# USB2DAC_PCB.net
KiCad netlist of a schematic drawn in EAGLE
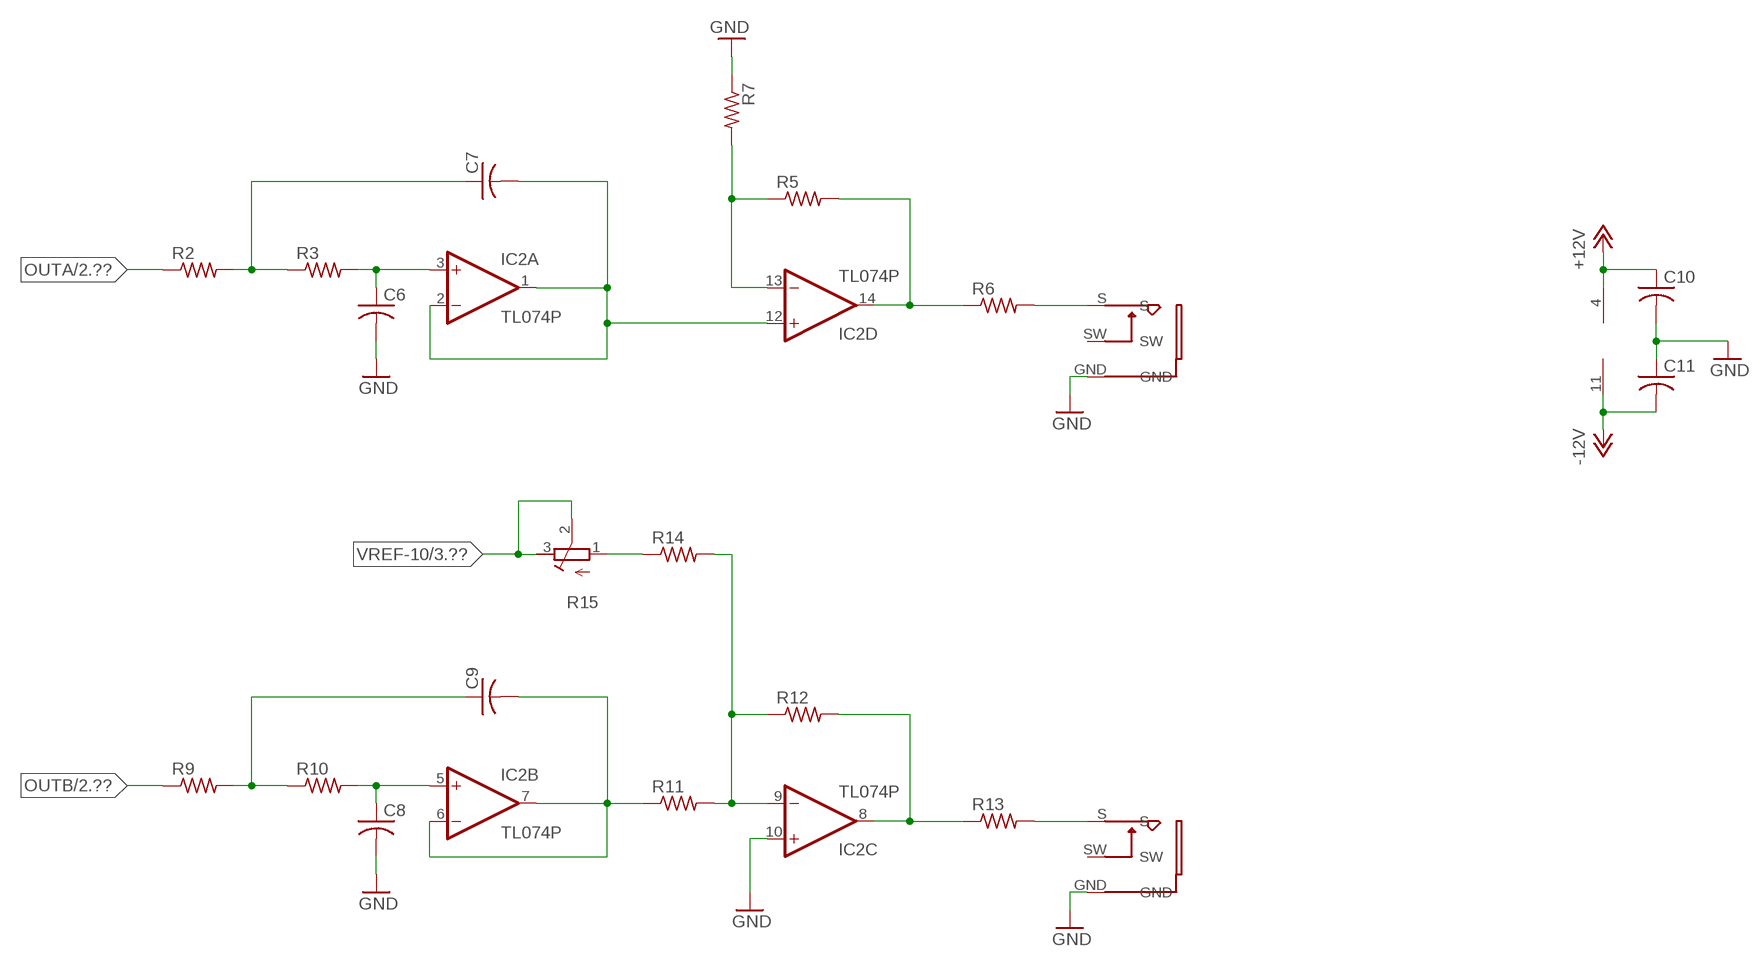
[diagram p0: schematic, sheet 1]
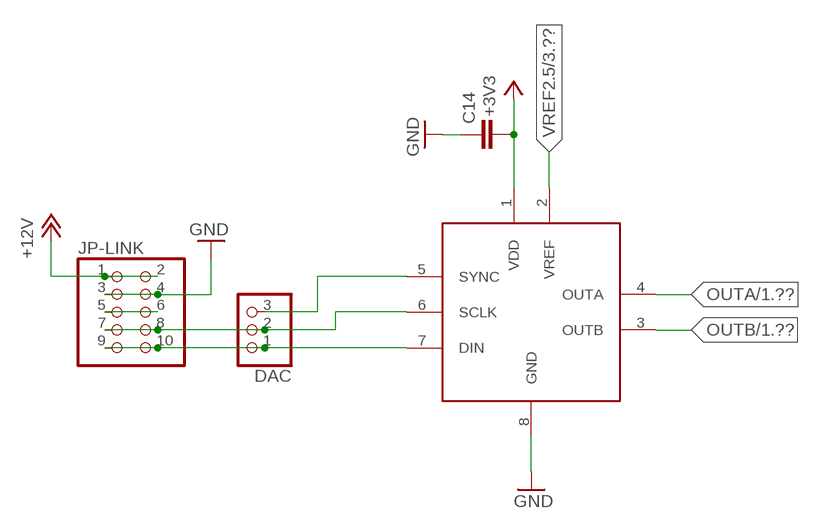
[diagram p1: schematic, sheet 2]
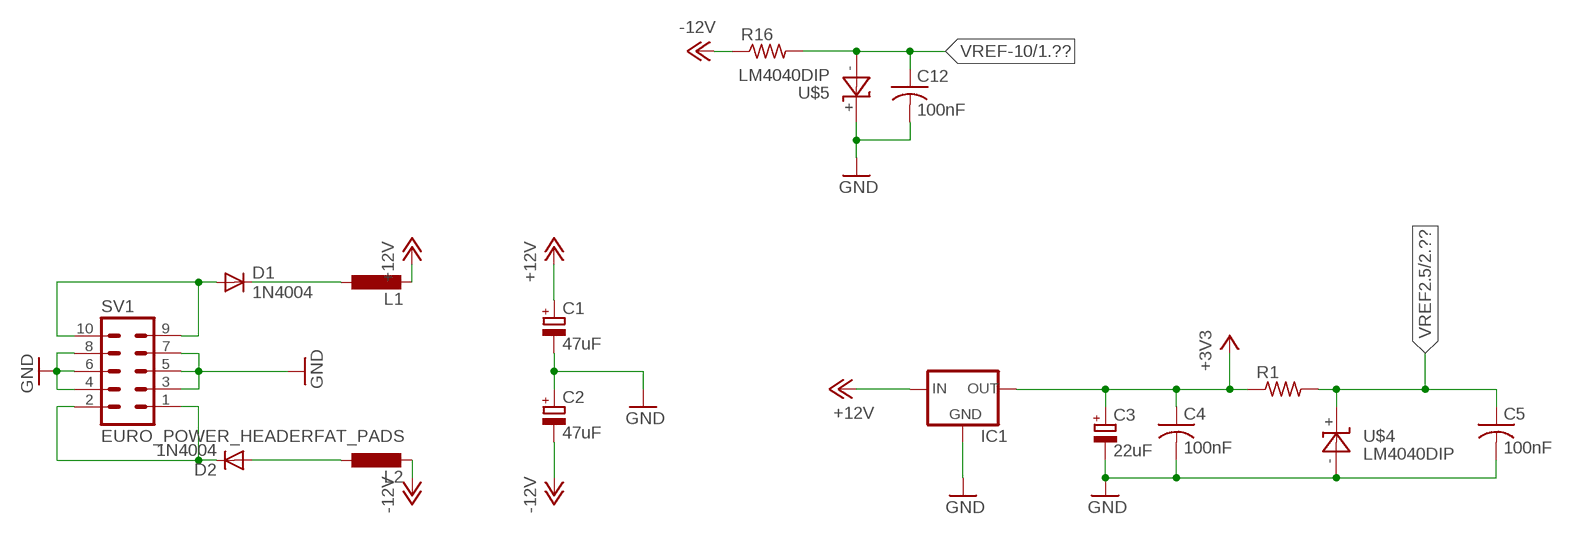
[diagram p2: schematic, sheet 3]
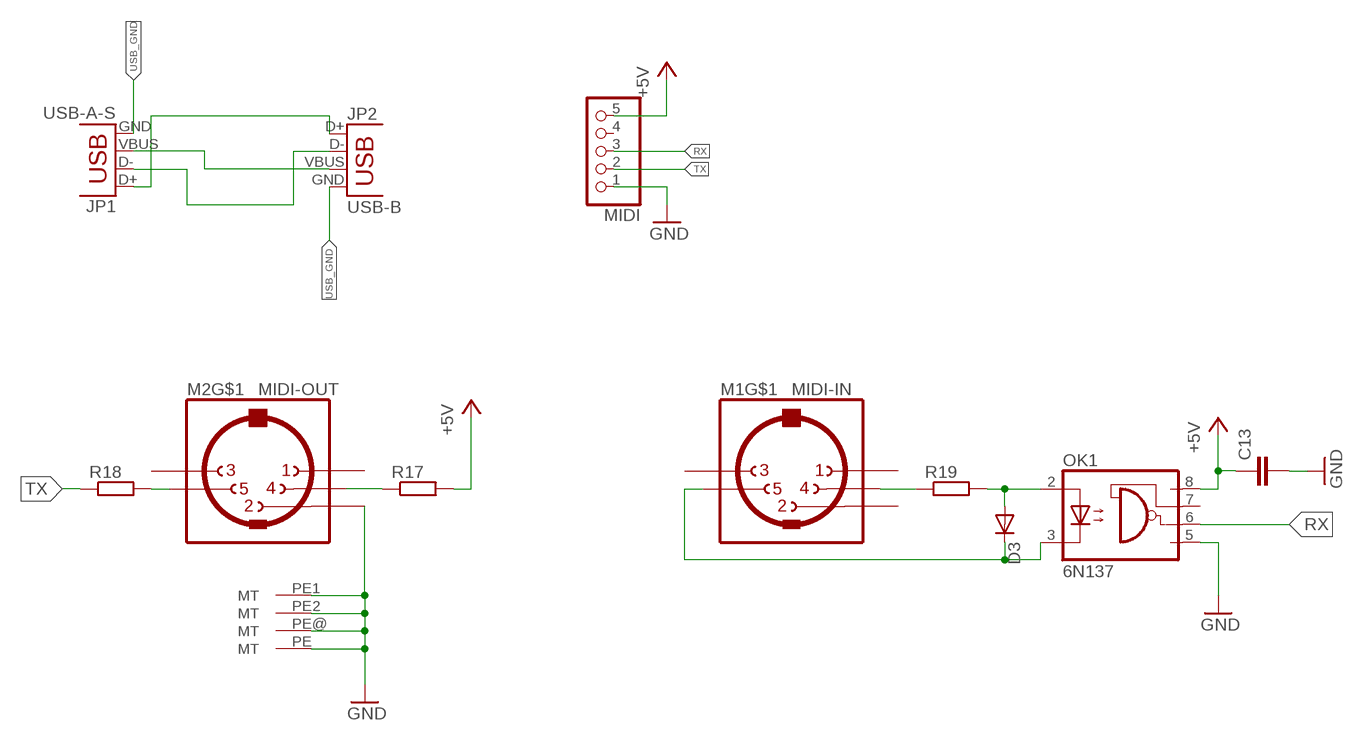
[diagram p3: schematic, sheet 4]

(export (version "E")
  (design (tool "Eeschema 10.0.6"))
  (components
    (comp (ref "C1")
      (value "47uF")
      (footprint "eagle-import:E2-5")
      (libsource (lib "eagle-import") (part "CPOL-EUE2-5"))
    )
    (comp (ref "C2")
      (value "47uF")
      (footprint "eagle-import:E2-5")
      (libsource (lib "eagle-import") (part "CPOL-EUE2-5"))
    )
    (comp (ref "C3")
      (value "22uF")
      (footprint "eagle-import:E2-5")
      (libsource (lib "eagle-import") (part "CPOL-EUE2-5"))
    )
    (comp (ref "C4")
      (value "100nF")
      (footprint "eagle-import:C1206K")
      (libsource (lib "eagle-import") (part "C-USC1206K"))
    )
    (comp (ref "C5")
      (value "100nF")
      (footprint "eagle-import:C1206K")
      (libsource (lib "eagle-import") (part "C-USC1206K"))
    )
    (comp (ref "C12")
      (value "100nF")
      (footprint "eagle-import:C1206K")
      (libsource (lib "eagle-import") (part "C-USC1206K"))
    )
    (comp (ref "D1")
      (value "1N4004")
      (footprint "eagle-import:DO41-10")
      (libsource (lib "eagle-import") (part "1N4004"))
    )
    (comp (ref "D2")
      (value "1N4004")
      (footprint "eagle-import:DO41-10")
      (libsource (lib "eagle-import") (part "1N4004"))
    )
    (comp (ref "IC1")
      (value "78LXX")
      (footprint "eagle-import:78LXX")
      (libsource (lib "eagle-import") (part "78LXX"))
    )
    (comp (ref "L1")
      (value "L-EU0207/10")
      (footprint "eagle-import:0207_10")
      (libsource (lib "eagle-import") (part "L-EU0207/10"))
    )
    (comp (ref "L2")
      (value "L-EU0207/10")
      (footprint "eagle-import:0207_10")
      (libsource (lib "eagle-import") (part "L-EU0207/10"))
    )
    (comp (ref "R1")
      (value "R-US_R1206")
      (footprint "eagle-import:R1206")
      (libsource (lib "eagle-import") (part "R-US_R1206"))
    )
    (comp (ref "R16")
      (value "R-US_R1206")
      (footprint "eagle-import:R1206")
      (libsource (lib "eagle-import") (part "R-US_R1206"))
    )
    (comp (ref "SV1")
      (value "EURO_POWER_HEADERFAT_PADS")
      (footprint "eagle-import:EURO_PWR_HEADER_FAT")
      (libsource (lib "eagle-import") (part "EURO_POWER_HEADERFAT_PADS"))
    )
    (comp (ref "U$4")
      (value "LM4040DIP")
      (footprint "eagle-import:TO-92")
      (libsource (lib "eagle-import") (part "LM4040DIP"))
    )
    (comp (ref "U$5")
      (value "LM4040DIP")
      (footprint "eagle-import:TO-92")
      (libsource (lib "eagle-import") (part "LM4040DIP"))
    )
    (comp (ref "C13")
      (value "C-EUC1206K")
      (footprint "eagle-import:C1206K")
      (libsource (lib "eagle-import") (part "C-EUC1206K"))
    )
    (comp (ref "D3")
      (value "SMALL_DIODEDO35-7")
      (footprint "eagle-import:DO35-7")
      (libsource (lib "eagle-import") (part "SMALL_DIODEDO35-7"))
    )
    (comp (ref "JP1")
      (value "USB-A-S")
      (footprint "eagle-import:USB-A-S")
      (libsource (lib "eagle-import") (part "USB-A-S"))
    )
    (comp (ref "JP2")
      (value "USB-B")
      (footprint "eagle-import:USB-B-PTH")
      (libsource (lib "eagle-import") (part "USBPTH"))
    )
    (comp (ref "M1")
      (value "MIDI-IN")
      (footprint "eagle-import:CP-2350")
      (libsource (lib "eagle-import") (part "MIDIJACK"))
    )
    (comp (ref "M2")
      (value "MIDI-OUT")
      (footprint "eagle-import:CP-2350")
      (libsource (lib "eagle-import") (part "MIDIJACK"))
    )
    (comp (ref "MIDI")
      (value "PINHD-1X5_2.54")
      (footprint "eagle-import:1X05")
      (libsource (lib "eagle-import") (part "PINHD-1X5_2.54"))
    )
    (comp (ref "OK1")
      (value "6N137")
      (footprint "eagle-import:DIL08")
      (libsource (lib "eagle-import") (part "6N137"))
    )
    (comp (ref "R17")
      (value "R-EU_R1206")
      (footprint "eagle-import:R1206")
      (libsource (lib "eagle-import") (part "R-EU_R1206"))
    )
    (comp (ref "R18")
      (value "R-EU_R1206")
      (footprint "eagle-import:R1206")
      (libsource (lib "eagle-import") (part "R-EU_R1206"))
    )
    (comp (ref "R19")
      (value "R-EU_R1206")
      (footprint "eagle-import:R1206")
      (libsource (lib "eagle-import") (part "R-EU_R1206"))
    )
    (comp (ref "C6")
      (value "C-USC1206K")
      (footprint "eagle-import:C1206K")
      (libsource (lib "eagle-import") (part "C-USC1206K"))
    )
    (comp (ref "C7")
      (value "C-USC1206K")
      (footprint "eagle-import:C1206K")
      (libsource (lib "eagle-import") (part "C-USC1206K"))
    )
    (comp (ref "C8")
      (value "C-USC1206K")
      (footprint "eagle-import:C1206K")
      (libsource (lib "eagle-import") (part "C-USC1206K"))
    )
    (comp (ref "C9")
      (value "C-USC1206K")
      (footprint "eagle-import:C1206K")
      (libsource (lib "eagle-import") (part "C-USC1206K"))
    )
    (comp (ref "C10")
      (value "C-USC1206K")
      (footprint "eagle-import:C1206K")
      (libsource (lib "eagle-import") (part "C-USC1206K"))
    )
    (comp (ref "C11")
      (value "C-USC1206K")
      (footprint "eagle-import:C1206K")
      (libsource (lib "eagle-import") (part "C-USC1206K"))
    )
    (comp (ref "IC2")
      (value "TL074P")
      (footprint "eagle-import:DIL14")
      (libsource (lib "eagle-import") (part "TL074P"))
    )
    (comp (ref "OUT1")
      (value "PJ302M")
      (footprint "eagle-import:PJ302M")
      (libsource (lib "eagle-import") (part "PJ302M"))
    )
    (comp (ref "OUT2")
      (value "PJ302M")
      (footprint "eagle-import:PJ302M")
      (libsource (lib "eagle-import") (part "PJ302M"))
    )
    (comp (ref "R2")
      (value "R-US_R1206")
      (footprint "eagle-import:R1206")
      (libsource (lib "eagle-import") (part "R-US_R1206"))
    )
    (comp (ref "R3")
      (value "R-US_R1206")
      (footprint "eagle-import:R1206")
      (libsource (lib "eagle-import") (part "R-US_R1206"))
    )
    (comp (ref "R5")
      (value "R-US_R1206")
      (footprint "eagle-import:R1206")
      (libsource (lib "eagle-import") (part "R-US_R1206"))
    )
    (comp (ref "R6")
      (value "R-US_R1206")
      (footprint "eagle-import:R1206")
      (libsource (lib "eagle-import") (part "R-US_R1206"))
    )
    (comp (ref "R7")
      (value "R-US_R1206")
      (footprint "eagle-import:R1206")
      (libsource (lib "eagle-import") (part "R-US_R1206"))
    )
    (comp (ref "R9")
      (value "R-US_R1206")
      (footprint "eagle-import:R1206")
      (libsource (lib "eagle-import") (part "R-US_R1206"))
    )
    (comp (ref "R10")
      (value "R-US_R1206")
      (footprint "eagle-import:R1206")
      (libsource (lib "eagle-import") (part "R-US_R1206"))
    )
    (comp (ref "R11")
      (value "R-US_R1206")
      (footprint "eagle-import:R1206")
      (libsource (lib "eagle-import") (part "R-US_R1206"))
    )
    (comp (ref "R12")
      (value "R-US_R1206")
      (footprint "eagle-import:R1206")
      (libsource (lib "eagle-import") (part "R-US_R1206"))
    )
    (comp (ref "R13")
      (value "R-US_R1206")
      (footprint "eagle-import:R1206")
      (libsource (lib "eagle-import") (part "R-US_R1206"))
    )
    (comp (ref "R14")
      (value "R-US_R1206")
      (footprint "eagle-import:R1206")
      (libsource (lib "eagle-import") (part "R-US_R1206"))
    )
    (comp (ref "R15")
      (value "R-TRIMM3296P")
      (footprint "eagle-import:RTRIM3296P")
      (libsource (lib "eagle-import") (part "R-TRIMM3296P"))
    )
    (comp (ref "C14")
      (value "C-EUC1206K")
      (footprint "eagle-import:C1206K")
      (libsource (lib "eagle-import") (part "C-EUC1206K"))
    )
    (comp (ref "DAC")
      (value "PINHD-1X3_2.54")
      (footprint "eagle-import:1X03")
      (libsource (lib "eagle-import") (part "PINHD-1X3_2.54"))
    )
    (comp (ref "JP-LINK")
      (value "PINHD-2X5_2.54")
      (footprint "eagle-import:2X05")
      (libsource (lib "eagle-import") (part "PINHD-2X5_2.54"))
    )
    (comp (ref "U$1")
      (value "DAC8552")
      (footprint "eagle-import:MSOP-8")
      (libsource (lib "eagle-import") (part "DAC8552"))
    )
  )
  (nets
    (net (code "1") (name "+3V3") (class "Default")
      (node (ref "C14") (pin "2") (pinfunction "2_2") (pintype "passive"))
      (node (ref "C3") (pin "+") (pinfunction "+_+") (pintype "passive"))
      (node (ref "C4") (pin "1") (pinfunction "1_1") (pintype "passive"))
      (node (ref "IC1") (pin "OUT") (pinfunction "OUT_OUT") (pintype "passive"))
      (node (ref "R1") (pin "1") (pinfunction "1_1") (pintype "passive"))
      (node (ref "U$1") (pin "1") (pinfunction "VDD_1") (pintype "bidirectional"))
    )
    (net (code "2") (name "+5V") (class "Default")
      (node (ref "C13") (pin "1") (pinfunction "1_1") (pintype "passive"))
      (node (ref "MIDI") (pin "5") (pinfunction "5_5") (pintype "passive"))
      (node (ref "OK1") (pin "8") (pinfunction "VCC_8") (pintype "passive"))
      (node (ref "R17") (pin "2") (pinfunction "2_2") (pintype "passive"))
    )
    (net (code "3") (name "+12V") (class "Default")
      (node (ref "C1") (pin "+") (pinfunction "+_+") (pintype "passive"))
      (node (ref "C10") (pin "1") (pinfunction "1_1") (pintype "passive"))
      (node (ref "IC1") (pin "IN") (pinfunction "IN_IN") (pintype "input"))
      (node (ref "IC2") (pin "4") (pinfunction "V+_4") (pintype "power_in"))
      (node (ref "JP-LINK") (pin "1") (pinfunction "1_1") (pintype "passive"))
      (node (ref "JP-LINK") (pin "2") (pinfunction "2_2") (pintype "passive"))
      (node (ref "L1") (pin "2") (pinfunction "2_2") (pintype "passive"))
    )
    (net (code "4") (name "-12V") (class "Default")
      (node (ref "C11") (pin "2") (pinfunction "2_2") (pintype "passive"))
      (node (ref "C2") (pin "-") (pinfunction "-_-") (pintype "passive"))
      (node (ref "IC2") (pin "11") (pinfunction "V-_11") (pintype "power_in"))
      (node (ref "L2") (pin "2") (pinfunction "2_2") (pintype "passive"))
      (node (ref "R16") (pin "1") (pinfunction "1_1") (pintype "passive"))
    )
    (net (code "5") (name "GND") (class "Default")
      (node (ref "C1") (pin "-") (pinfunction "-_-") (pintype "passive"))
      (node (ref "C10") (pin "2") (pinfunction "2_2") (pintype "passive"))
      (node (ref "C11") (pin "1") (pinfunction "1_1") (pintype "passive"))
      (node (ref "C12") (pin "2") (pinfunction "2_2") (pintype "passive"))
      (node (ref "C13") (pin "2") (pinfunction "2_2") (pintype "passive"))
      (node (ref "C14") (pin "1") (pinfunction "1_1") (pintype "passive"))
      (node (ref "C2") (pin "+") (pinfunction "+_+") (pintype "passive"))
      (node (ref "C3") (pin "-") (pinfunction "-_-") (pintype "passive"))
      (node (ref "C4") (pin "2") (pinfunction "2_2") (pintype "passive"))
      (node (ref "C5") (pin "2") (pinfunction "2_2") (pintype "passive"))
      (node (ref "C6") (pin "2") (pinfunction "2_2") (pintype "passive"))
      (node (ref "C8") (pin "2") (pinfunction "2_2") (pintype "passive"))
      (node (ref "IC1") (pin "GND") (pinfunction "GND_GND") (pintype "input"))
      (node (ref "IC2") (pin "10") (pinfunction "+IN_10") (pintype "input"))
      (node (ref "JP-LINK") (pin "3") (pinfunction "3_3") (pintype "passive"))
      (node (ref "JP-LINK") (pin "4") (pinfunction "4_4") (pintype "passive"))
      (node (ref "M2") (pin "2") (pinfunction "2_2") (pintype "passive"))
      (node (ref "M2") (pin "PE") (pinfunction "MT_PE") (pintype "passive"))
      (node (ref "M2") (pin "PE1") (pinfunction "MT_PE1") (pintype "passive"))
      (node (ref "M2") (pin "PE2") (pinfunction "MT_PE2") (pintype "passive"))
      (node (ref "M2") (pin "PE@") (pinfunction "MT_PE@") (pintype "passive"))
      (node (ref "MIDI") (pin "1") (pinfunction "1_1") (pintype "passive"))
      (node (ref "OK1") (pin "5") (pinfunction "GND_5") (pintype "passive"))
      (node (ref "OUT1") (pin "GND") (pinfunction "GND_GND") (pintype "bidirectional"))
      (node (ref "OUT2") (pin "GND") (pinfunction "GND_GND") (pintype "bidirectional"))
      (node (ref "R7") (pin "1") (pinfunction "1_1") (pintype "passive"))
      (node (ref "SV1") (pin "3") (pinfunction "3_3") (pintype "passive"))
      (node (ref "SV1") (pin "4") (pinfunction "4_4") (pintype "passive"))
      (node (ref "SV1") (pin "5") (pinfunction "5_5") (pintype "passive"))
      (node (ref "SV1") (pin "6") (pinfunction "6_6") (pintype "passive"))
      (node (ref "SV1") (pin "7") (pinfunction "7_7") (pintype "passive"))
      (node (ref "SV1") (pin "8") (pinfunction "8_8") (pintype "passive"))
      (node (ref "U$1") (pin "8") (pinfunction "GND_8") (pintype "bidirectional"))
      (node (ref "U$4") (pin "-") (pinfunction "-_-") (pintype "output"))
      (node (ref "U$5") (pin "+") (pinfunction "+_+") (pintype "input"))
    )
    (net (code "6") (name "Net-(C7-Pad1)") (class "Default")
      (node (ref "C7") (pin "1") (pinfunction "1_1") (pintype "passive"))
      (node (ref "R2") (pin "2") (pinfunction "2_2") (pintype "passive"))
      (node (ref "R3") (pin "1") (pinfunction "1_1") (pintype "passive"))
    )
    (net (code "7") (name "Net-(C9-Pad1)") (class "Default")
      (node (ref "C9") (pin "1") (pinfunction "1_1") (pintype "passive"))
      (node (ref "R10") (pin "1") (pinfunction "1_1") (pintype "passive"))
      (node (ref "R9") (pin "2") (pinfunction "2_2") (pintype "passive"))
    )
    (net (code "8") (name "Net-(D1-PadA)") (class "Default")
      (node (ref "D1") (pin "A") (pinfunction "A_A") (pintype "passive"))
      (node (ref "SV1") (pin "10") (pinfunction "10_10") (pintype "passive"))
      (node (ref "SV1") (pin "9") (pinfunction "9_9") (pintype "passive"))
    )
    (net (code "9") (name "Net-(D1-PadC)") (class "Default")
      (node (ref "D1") (pin "C") (pinfunction "C_C") (pintype "passive"))
      (node (ref "L1") (pin "1") (pinfunction "1_1") (pintype "passive"))
    )
    (net (code "10") (name "Net-(D2-PadA)") (class "Default")
      (node (ref "D2") (pin "A") (pinfunction "A_A") (pintype "passive"))
      (node (ref "L2") (pin "1") (pinfunction "1_1") (pintype "passive"))
    )
    (net (code "11") (name "Net-(D2-PadC)") (class "Default")
      (node (ref "D2") (pin "C") (pinfunction "C_C") (pintype "passive"))
      (node (ref "SV1") (pin "1") (pinfunction "1_1") (pintype "passive"))
      (node (ref "SV1") (pin "2") (pinfunction "2_2") (pintype "passive"))
    )
    (net (code "12") (name "Net-(IC2A-+IN)") (class "Default")
      (node (ref "C6") (pin "1") (pinfunction "1_1") (pintype "passive"))
      (node (ref "IC2") (pin "3") (pinfunction "+IN_3") (pintype "input"))
      (node (ref "R3") (pin "2") (pinfunction "2_2") (pintype "passive"))
    )
    (net (code "13") (name "Net-(IC2A--IN)") (class "Default")
      (node (ref "C7") (pin "2") (pinfunction "2_2") (pintype "passive"))
      (node (ref "IC2") (pin "1") (pinfunction "OUT_1") (pintype "output"))
      (node (ref "IC2") (pin "12") (pinfunction "+IN_12") (pintype "input"))
      (node (ref "IC2") (pin "2") (pinfunction "-IN_2") (pintype "input"))
    )
    (net (code "14") (name "Net-(IC2B-+IN)") (class "Default")
      (node (ref "C8") (pin "1") (pinfunction "1_1") (pintype "passive"))
      (node (ref "IC2") (pin "5") (pinfunction "+IN_5") (pintype "input"))
      (node (ref "R10") (pin "2") (pinfunction "2_2") (pintype "passive"))
    )
    (net (code "15") (name "Net-(IC2B--IN)") (class "Default")
      (node (ref "C9") (pin "2") (pinfunction "2_2") (pintype "passive"))
      (node (ref "IC2") (pin "6") (pinfunction "-IN_6") (pintype "input"))
      (node (ref "IC2") (pin "7") (pinfunction "OUT_7") (pintype "output"))
      (node (ref "R11") (pin "1") (pinfunction "1_1") (pintype "passive"))
    )
    (net (code "16") (name "Net-(IC2C--IN)") (class "Default")
      (node (ref "IC2") (pin "9") (pinfunction "-IN_9") (pintype "input"))
      (node (ref "R11") (pin "2") (pinfunction "2_2") (pintype "passive"))
      (node (ref "R12") (pin "1") (pinfunction "1_1") (pintype "passive"))
      (node (ref "R14") (pin "2") (pinfunction "2_2") (pintype "passive"))
    )
    (net (code "17") (name "Net-(IC2C-OUT)") (class "Default")
      (node (ref "IC2") (pin "8") (pinfunction "OUT_8") (pintype "output"))
      (node (ref "R12") (pin "2") (pinfunction "2_2") (pintype "passive"))
      (node (ref "R13") (pin "1") (pinfunction "1_1") (pintype "passive"))
    )
    (net (code "18") (name "Net-(IC2D--IN)") (class "Default")
      (node (ref "IC2") (pin "13") (pinfunction "-IN_13") (pintype "input"))
      (node (ref "R5") (pin "1") (pinfunction "1_1") (pintype "passive"))
      (node (ref "R7") (pin "2") (pinfunction "2_2") (pintype "passive"))
    )
    (net (code "19") (name "Net-(IC2D-OUT)") (class "Default")
      (node (ref "IC2") (pin "14") (pinfunction "OUT_14") (pintype "output"))
      (node (ref "R5") (pin "2") (pinfunction "2_2") (pintype "passive"))
      (node (ref "R6") (pin "1") (pinfunction "1_1") (pintype "passive"))
    )
    (net (code "20") (name "Net-(JP-LINK-Pad5)") (class "Default")
      (node (ref "JP-LINK") (pin "5") (pinfunction "5_5") (pintype "passive"))
      (node (ref "JP-LINK") (pin "6") (pinfunction "6_6") (pintype "passive"))
    )
    (net (code "21") (name "Net-(JP1-PadD+)") (class "Default")
      (node (ref "JP1") (pin "D+") (pinfunction "D+_D+") (pintype "bidirectional"))
      (node (ref "JP2") (pin "D+") (pinfunction "D+_D+") (pintype "bidirectional"))
    )
    (net (code "22") (name "Net-(JP1-PadD-)") (class "Default")
      (node (ref "JP1") (pin "D-") (pinfunction "D-_D-") (pintype "bidirectional"))
      (node (ref "JP2") (pin "D-") (pinfunction "D-_D-") (pintype "bidirectional"))
    )
    (net (code "23") (name "Net-(JP1-PadVBUS)") (class "Default")
      (node (ref "JP1") (pin "VBUS") (pinfunction "VBUS_VBUS") (pintype "bidirectional"))
      (node (ref "JP2") (pin "VBUS") (pinfunction "VBUS_VBUS") (pintype "bidirectional"))
    )
    (net (code "24") (name "Net-(M1-Pad4)") (class "Default")
      (node (ref "M1") (pin "4") (pinfunction "4_4") (pintype "passive"))
      (node (ref "R19") (pin "1") (pinfunction "1_1") (pintype "passive"))
    )
    (net (code "25") (name "Net-(M2-Pad4)") (class "Default")
      (node (ref "M2") (pin "4") (pinfunction "4_4") (pintype "passive"))
      (node (ref "R17") (pin "1") (pinfunction "1_1") (pintype "passive"))
    )
    (net (code "26") (name "Net-(M2-Pad5)") (class "Default")
      (node (ref "M2") (pin "5") (pinfunction "5_5") (pintype "passive"))
      (node (ref "R18") (pin "2") (pinfunction "2_2") (pintype "passive"))
    )
    (net (code "27") (name "Net-(OK1-A)") (class "Default")
      (node (ref "D3") (pin "A") (pinfunction "A_A") (pintype "passive"))
      (node (ref "OK1") (pin "2") (pinfunction "A_2") (pintype "passive"))
      (node (ref "R19") (pin "2") (pinfunction "2_2") (pintype "passive"))
    )
    (net (code "28") (name "Net-(OK1-C)") (class "Default")
      (node (ref "D3") (pin "C") (pinfunction "C_C") (pintype "passive"))
      (node (ref "M1") (pin "5") (pinfunction "5_5") (pintype "passive"))
      (node (ref "OK1") (pin "3") (pinfunction "C_3") (pintype "passive"))
    )
    (net (code "29") (name "Net-(OUT1-PadS)") (class "Default")
      (node (ref "OUT1") (pin "S") (pinfunction "S_S") (pintype "bidirectional"))
      (node (ref "R6") (pin "2") (pinfunction "2_2") (pintype "passive"))
    )
    (net (code "30") (name "Net-(OUT2-PadS)") (class "Default")
      (node (ref "OUT2") (pin "S") (pinfunction "S_S") (pintype "bidirectional"))
      (node (ref "R13") (pin "2") (pinfunction "2_2") (pintype "passive"))
    )
    (net (code "31") (name "Net-(R15-E)") (class "Default")
      (node (ref "R14") (pin "1") (pinfunction "1_1") (pintype "passive"))
      (node (ref "R15") (pin "1") (pinfunction "E_1") (pintype "passive"))
    )
    (net (code "32") (name "Net-(U$1-DIN)") (class "Default")
      (node (ref "DAC") (pin "1") (pinfunction "1_1") (pintype "passive"))
      (node (ref "JP-LINK") (pin "10") (pinfunction "10_10") (pintype "passive"))
      (node (ref "JP-LINK") (pin "9") (pinfunction "9_9") (pintype "passive"))
      (node (ref "U$1") (pin "7") (pinfunction "DIN_7") (pintype "bidirectional"))
    )
    (net (code "33") (name "Net-(U$1-SCLK)") (class "Default")
      (node (ref "DAC") (pin "2") (pinfunction "2_2") (pintype "passive"))
      (node (ref "JP-LINK") (pin "7") (pinfunction "7_7") (pintype "passive"))
      (node (ref "JP-LINK") (pin "8") (pinfunction "8_8") (pintype "passive"))
      (node (ref "U$1") (pin "6") (pinfunction "SCLK_6") (pintype "bidirectional"))
    )
    (net (code "34") (name "Net-(U$1-SYNC)") (class "Default")
      (node (ref "DAC") (pin "3") (pinfunction "3_3") (pintype "passive"))
      (node (ref "U$1") (pin "5") (pinfunction "SYNC_5") (pintype "bidirectional"))
    )
    (net (code "35") (name "OUTA") (class "Default")
      (node (ref "R2") (pin "1") (pinfunction "1_1") (pintype "passive"))
      (node (ref "U$1") (pin "4") (pinfunction "OUTA_4") (pintype "bidirectional"))
    )
    (net (code "36") (name "OUTB") (class "Default")
      (node (ref "R9") (pin "1") (pinfunction "1_1") (pintype "passive"))
      (node (ref "U$1") (pin "3") (pinfunction "OUTB_3") (pintype "bidirectional"))
    )
    (net (code "37") (name "RX") (class "Default")
      (node (ref "MIDI") (pin "3") (pinfunction "3_3") (pintype "passive"))
      (node (ref "OK1") (pin "6") (pinfunction "VO_6") (pintype "passive"))
    )
    (net (code "38") (name "TX") (class "Default")
      (node (ref "MIDI") (pin "2") (pinfunction "2_2") (pintype "passive"))
      (node (ref "R18") (pin "1") (pinfunction "1_1") (pintype "passive"))
    )
    (net (code "39") (name "USB_GND") (class "Default")
      (node (ref "JP1") (pin "GND") (pinfunction "GND_GND") (pintype "bidirectional"))
      (node (ref "JP2") (pin "GND") (pinfunction "GND_GND") (pintype "bidirectional"))
    )
    (net (code "40") (name "VREF-10") (class "Default")
      (node (ref "C12") (pin "1") (pinfunction "1_1") (pintype "passive"))
      (node (ref "R15") (pin "2") (pinfunction "S_2") (pintype "passive"))
      (node (ref "R15") (pin "3") (pinfunction "A_3") (pintype "passive"))
      (node (ref "R16") (pin "2") (pinfunction "2_2") (pintype "passive"))
      (node (ref "U$5") (pin "-") (pinfunction "-_-") (pintype "output"))
    )
    (net (code "41") (name "VREF2.5") (class "Default")
      (node (ref "C5") (pin "1") (pinfunction "1_1") (pintype "passive"))
      (node (ref "R1") (pin "2") (pinfunction "2_2") (pintype "passive"))
      (node (ref "U$1") (pin "2") (pinfunction "VREF_2") (pintype "bidirectional"))
      (node (ref "U$4") (pin "+") (pinfunction "+_+") (pintype "input"))
    )
    (net (code "42") (name "unconnected-(M1-Pad1)") (class "Default")
      (node (ref "M1") (pin "1") (pinfunction "1_1") (pintype "passive"))
    )
    (net (code "43") (name "unconnected-(M1-Pad2)") (class "Default")
      (node (ref "M1") (pin "2") (pinfunction "2_2") (pintype "passive"))
    )
    (net (code "44") (name "unconnected-(M1-Pad3)") (class "Default")
      (node (ref "M1") (pin "3") (pinfunction "3_3") (pintype "passive"))
    )
    (net (code "45") (name "unconnected-(M2-Pad1)") (class "Default")
      (node (ref "M2") (pin "1") (pinfunction "1_1") (pintype "passive"))
    )
    (net (code "46") (name "unconnected-(M2-Pad3)") (class "Default")
      (node (ref "M2") (pin "3") (pinfunction "3_3") (pintype "passive"))
    )
    (net (code "47") (name "unconnected-(MIDI-Pad4)") (class "Default")
      (node (ref "MIDI") (pin "4") (pinfunction "4_4") (pintype "passive"))
    )
    (net (code "48") (name "unconnected-(OK1-VE-Pad7)") (class "Default")
      (node (ref "OK1") (pin "7") (pinfunction "VE_7") (pintype "passive"))
    )
    (net (code "49") (name "unconnected-(OUT1-PadSW)") (class "Default")
      (node (ref "OUT1") (pin "SW") (pinfunction "SW_SW") (pintype "bidirectional"))
    )
    (net (code "50") (name "unconnected-(OUT2-PadSW)") (class "Default")
      (node (ref "OUT2") (pin "SW") (pinfunction "SW_SW") (pintype "bidirectional"))
    )
  )
)
